# Older_Schematic.net
KiCad netlist of a schematic drawn in EAGLE
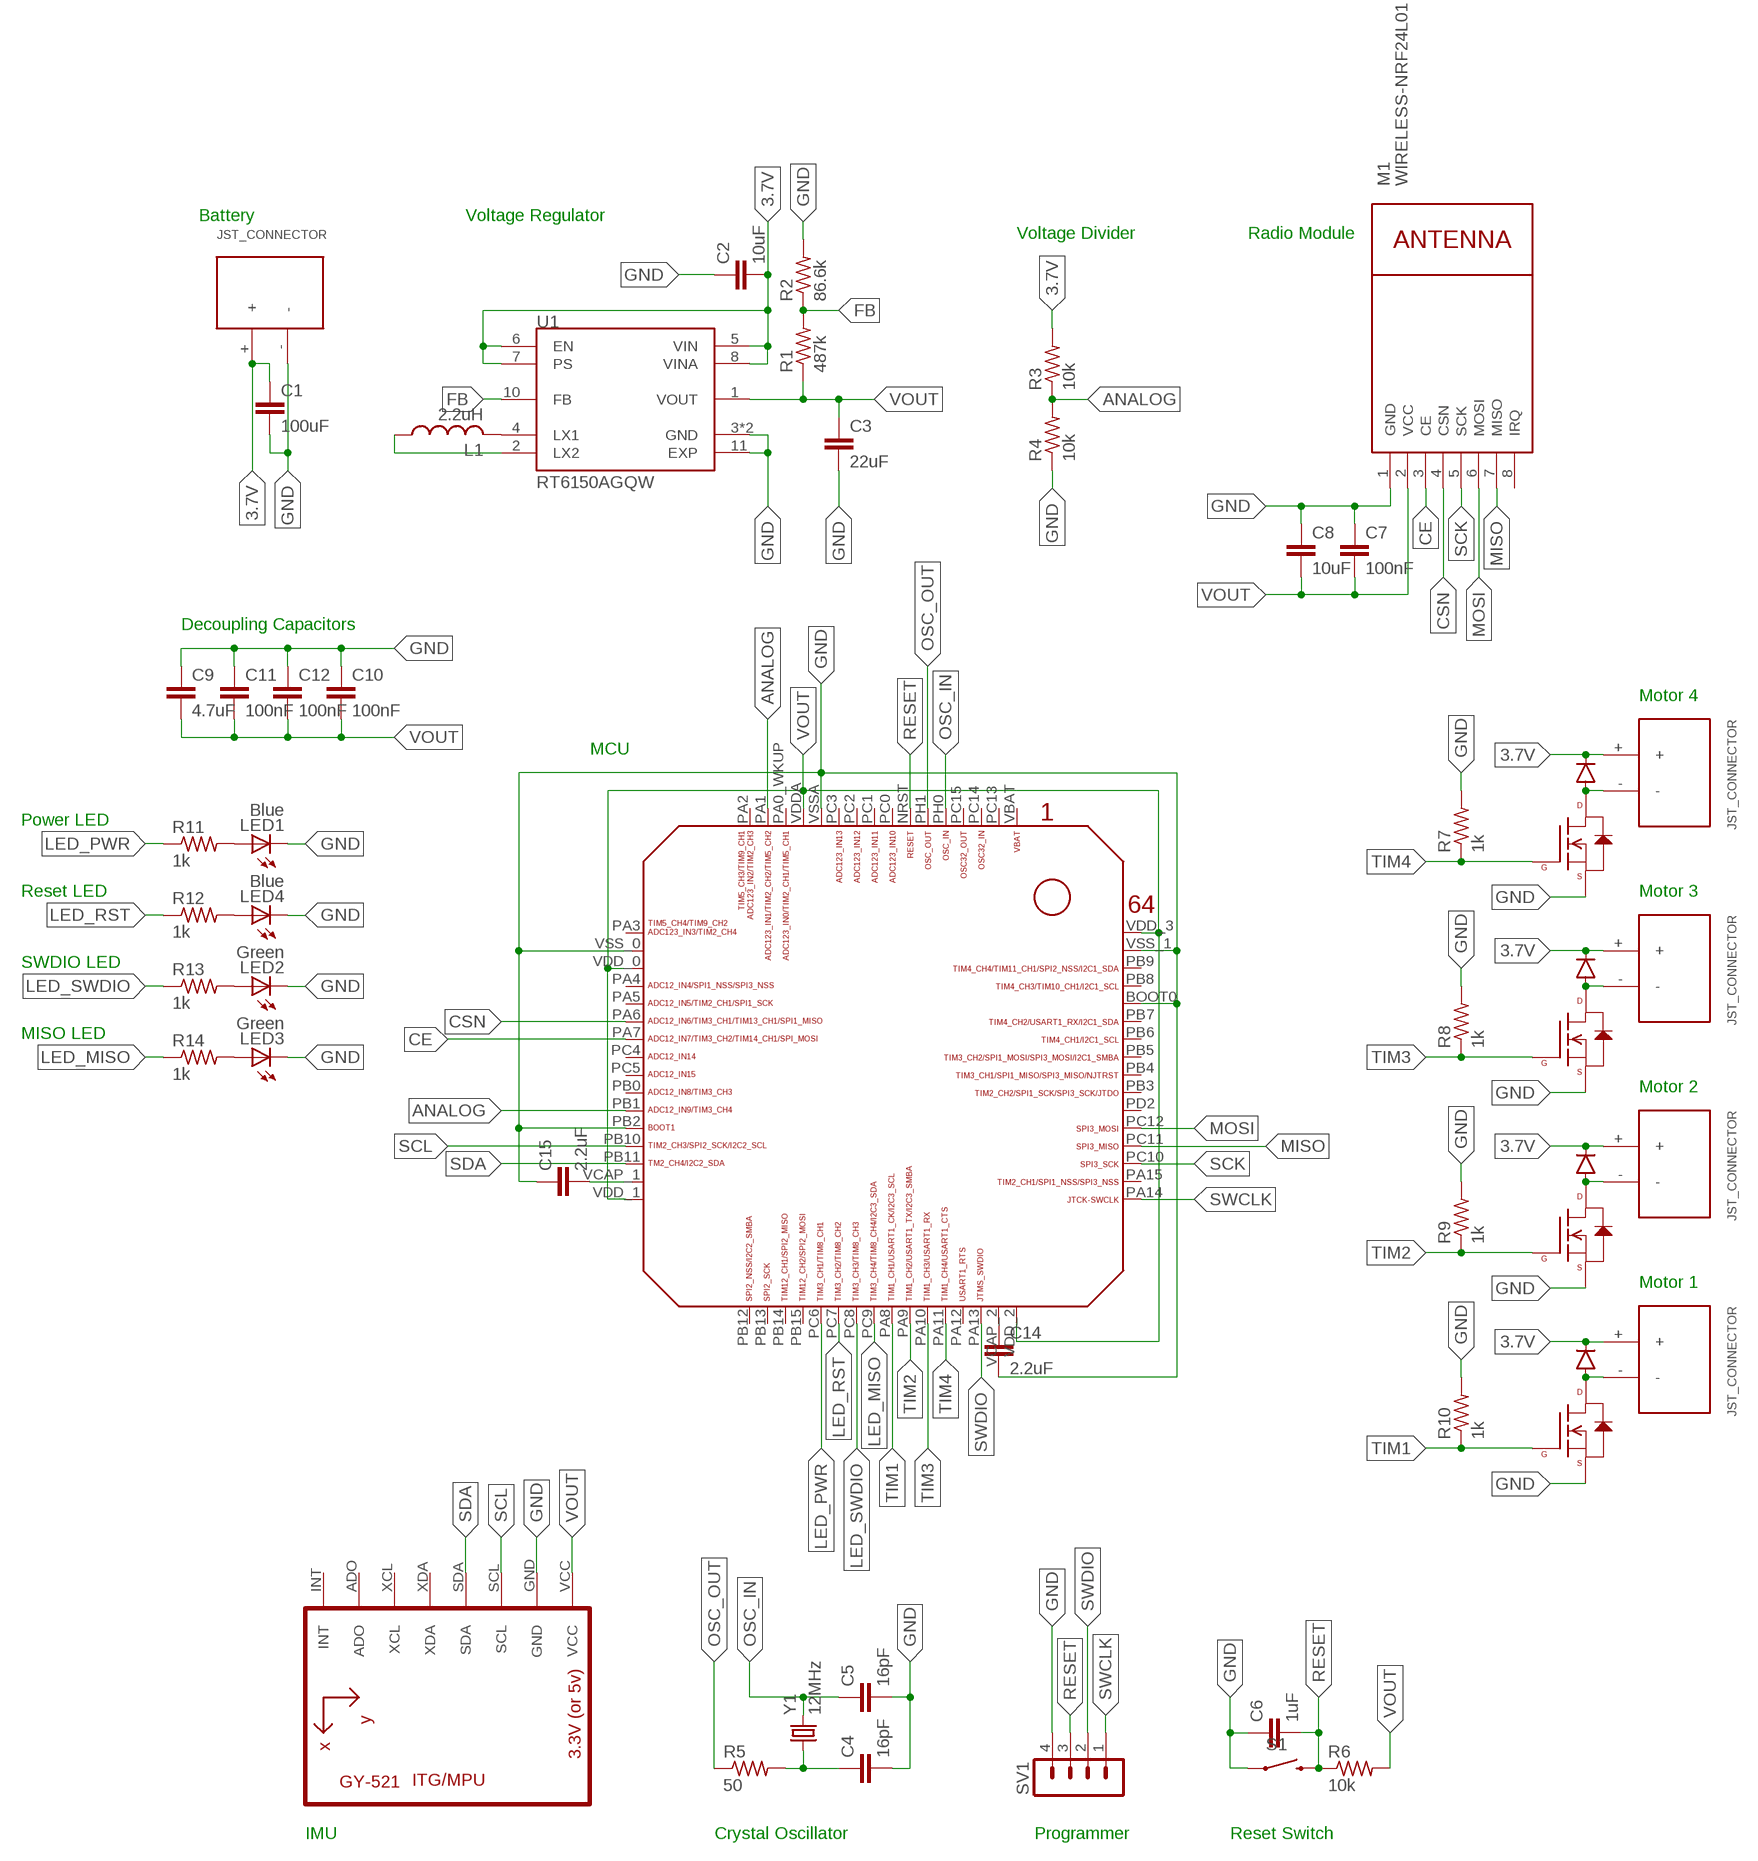
[diagram p0: schematic, sheet 1]

(export (version "E")
  (design (tool "Eeschema 10.0.6"))
  (components
    (comp (ref "C1")
      (value "100uF")
      (footprint "eagle-import:C0603")
      (libsource (lib "eagle-import") (part "rcl_334_C-EUC0603"))
    )
    (comp (ref "C2")
      (value "10uF")
      (footprint "eagle-import:C0603")
      (libsource (lib "eagle-import") (part "rcl_334_C-EUC0603"))
    )
    (comp (ref "C3")
      (value "22uF")
      (footprint "eagle-import:C0603")
      (libsource (lib "eagle-import") (part "rcl_334_C-EUC0603"))
    )
    (comp (ref "C4")
      (value "16pF")
      (footprint "eagle-import:C0603")
      (libsource (lib "eagle-import") (part "rcl_334_C-EUC0603"))
    )
    (comp (ref "C5")
      (value "16pF")
      (footprint "eagle-import:C0603")
      (libsource (lib "eagle-import") (part "rcl_334_C-EUC0603"))
    )
    (comp (ref "C6")
      (value "1uF")
      (footprint "eagle-import:C0603")
      (libsource (lib "eagle-import") (part "rcl_334_C-EUC0603"))
    )
    (comp (ref "C7")
      (value "100nF")
      (footprint "eagle-import:C0603")
      (libsource (lib "eagle-import") (part "rcl_334_C-EUC0603"))
    )
    (comp (ref "C8")
      (value "10uF")
      (footprint "eagle-import:C0603")
      (libsource (lib "eagle-import") (part "rcl_334_C-EUC0603"))
    )
    (comp (ref "C9")
      (value "4.7uF")
      (footprint "eagle-import:C0603")
      (libsource (lib "eagle-import") (part "rcl_334_C-EUC0603"))
    )
    (comp (ref "C10")
      (value "100nF")
      (footprint "eagle-import:C0603")
      (libsource (lib "eagle-import") (part "rcl_334_C-EUC0603"))
    )
    (comp (ref "C11")
      (value "100nF")
      (footprint "eagle-import:C0603")
      (libsource (lib "eagle-import") (part "rcl_334_C-EUC0603"))
    )
    (comp (ref "C12")
      (value "100nF")
      (footprint "eagle-import:C0603")
      (libsource (lib "eagle-import") (part "rcl_334_C-EUC0603"))
    )
    (comp (ref "C14")
      (value "2.2uF")
      (footprint "eagle-import:C0603")
      (libsource (lib "eagle-import") (part "C-EUC0603"))
    )
    (comp (ref "C15")
      (value "2.2uF")
      (footprint "eagle-import:C0603")
      (libsource (lib "eagle-import") (part "C-EUC0603"))
    )
    (comp (ref "L1")
      (value "2.2uH")
      (footprint "eagle-import:L0603")
      (libsource (lib "eagle-import") (part "L-USL0603"))
    )
    (comp (ref "LED1")
      (value "Blue")
      (footprint "eagle-import:CHIP-LED0603")
      (libsource (lib "eagle-import") (part "LEDCHIP-LED0603"))
    )
    (comp (ref "LED2")
      (value "Green")
      (footprint "eagle-import:CHIP-LED0603")
      (libsource (lib "eagle-import") (part "LEDCHIP-LED0603"))
    )
    (comp (ref "LED3")
      (value "Green")
      (footprint "eagle-import:CHIP-LED0603")
      (libsource (lib "eagle-import") (part "LEDCHIP-LED0603"))
    )
    (comp (ref "LED4")
      (value "Blue")
      (footprint "eagle-import:CHIP-LED0603")
      (libsource (lib "eagle-import") (part "LEDCHIP-LED0603"))
    )
    (comp (ref "M1")
      (value "WIRELESS-NRF24L01")
      (footprint "eagle-import:WIRELESS-NRF24L01")
      (libsource (lib "eagle-import") (part "WIRELESS-NRF24L01"))
    )
    (comp (ref "R1")
      (value "487k")
      (footprint "eagle-import:R0603")
      (libsource (lib "eagle-import") (part "R-US_R0603"))
    )
    (comp (ref "R2")
      (value "86.6k")
      (footprint "eagle-import:R0603")
      (libsource (lib "eagle-import") (part "R-US_R0603"))
    )
    (comp (ref "R3")
      (value "10k")
      (footprint "eagle-import:R0603")
      (libsource (lib "eagle-import") (part "R-US_R0603"))
    )
    (comp (ref "R4")
      (value "10k")
      (footprint "eagle-import:R0603")
      (libsource (lib "eagle-import") (part "R-US_R0603"))
    )
    (comp (ref "R5")
      (value "50")
      (footprint "eagle-import:R0603")
      (libsource (lib "eagle-import") (part "R-US_R0603"))
    )
    (comp (ref "R6")
      (value "10k")
      (footprint "eagle-import:R0603")
      (libsource (lib "eagle-import") (part "R-US_R0603"))
    )
    (comp (ref "R7")
      (value "1k")
      (footprint "eagle-import:R0603")
      (libsource (lib "eagle-import") (part "R-US_R0603"))
    )
    (comp (ref "R8")
      (value "1k")
      (footprint "eagle-import:R0603")
      (libsource (lib "eagle-import") (part "R-US_R0603"))
    )
    (comp (ref "R9")
      (value "1k")
      (footprint "eagle-import:R0603")
      (libsource (lib "eagle-import") (part "R-US_R0603"))
    )
    (comp (ref "R10")
      (value "1k")
      (footprint "eagle-import:R0603")
      (libsource (lib "eagle-import") (part "R-US_R0603"))
    )
    (comp (ref "R11")
      (value "1k")
      (footprint "eagle-import:R0603")
      (libsource (lib "eagle-import") (part "R-US_R0603"))
    )
    (comp (ref "R12")
      (value "1k")
      (footprint "eagle-import:R0603")
      (libsource (lib "eagle-import") (part "R-US_R0603"))
    )
    (comp (ref "R13")
      (value "1k")
      (footprint "eagle-import:R0603")
      (libsource (lib "eagle-import") (part "R-US_R0603"))
    )
    (comp (ref "R14")
      (value "1k")
      (footprint "eagle-import:R0603")
      (libsource (lib "eagle-import") (part "R-US_R0603"))
    )
    (comp (ref "S1")
      (value "SWITCH-MOMENTARY-2SMD")
      (footprint "eagle-import:TACTILE-SWITCH-SMD")
      (libsource (lib "eagle-import") (part "SWITCH-MOMENTARY-2SMD"))
    )
    (comp (ref "SV1")
      (value "MA04-1")
      (footprint "eagle-import:MA04-1")
      (libsource (lib "eagle-import") (part "MA04-1"))
    )
    (comp (ref "U$1")
      (value "STM32F405/415_LQFP64")
      (footprint "eagle-import:STM32F405_415_LQFP64")
      (libsource (lib "eagle-import") (part "STM32F405/415_LQFP64"))
    )
    (comp (ref "U$2")
      (value "JST_CONNECTOR_FEMALE")
      (footprint "eagle-import:JST_CONNECTOR_FEMALE")
      (libsource (lib "eagle-import") (part "JST_CONNECTOR_FEMALE"))
    )
    (comp (ref "U$3")
      (value "JST_CONNECTOR_FEMALE")
      (footprint "eagle-import:JST_CONNECTOR_FEMALE")
      (libsource (lib "eagle-import") (part "JST_CONNECTOR_FEMALE"))
    )
    (comp (ref "U$4")
      (value "JST_CONNECTOR_FEMALE")
      (footprint "eagle-import:JST_CONNECTOR_FEMALE")
      (libsource (lib "eagle-import") (part "JST_CONNECTOR_FEMALE"))
    )
    (comp (ref "U$5")
      (value "JST_CONNECTOR_FEMALE")
      (footprint "eagle-import:JST_CONNECTOR_FEMALE")
      (libsource (lib "eagle-import") (part "JST_CONNECTOR_FEMALE"))
    )
    (comp (ref "U$6")
      (value "JST_CONNECTOR_FEMALE")
      (footprint "eagle-import:JST_CONNECTOR_FEMALE")
      (libsource (lib "eagle-import") (part "JST_CONNECTOR_FEMALE"))
    )
    (comp (ref "U$7")
      (value "N-CHANNEL-MOSFET-IRLML6244TRPBF")
      (footprint "eagle-import:SOT23-3")
      (libsource (lib "eagle-import") (part "N-CHANNEL-MOSFET-IRLML6244TRPBF"))
    )
    (comp (ref "U$8")
      (value "N-CHANNEL-MOSFET-IRLML6244TRPBF")
      (footprint "eagle-import:SOT23-3")
      (libsource (lib "eagle-import") (part "N-CHANNEL-MOSFET-IRLML6244TRPBF"))
    )
    (comp (ref "U$9")
      (value "N-CHANNEL-MOSFET-IRLML6244TRPBF")
      (footprint "eagle-import:SOT23-3")
      (libsource (lib "eagle-import") (part "N-CHANNEL-MOSFET-IRLML6244TRPBF"))
    )
    (comp (ref "U$10")
      (value "N-CHANNEL-MOSFET-IRLML6244TRPBF")
      (footprint "eagle-import:SOT23-3")
      (libsource (lib "eagle-import") (part "N-CHANNEL-MOSFET-IRLML6244TRPBF"))
    )
    (comp (ref "U$11")
      (value "DB2W40300L")
      (footprint "eagle-import:MINI2-F3-B")
      (libsource (lib "eagle-import") (part "DB2W40300L"))
    )
    (comp (ref "U$12")
      (value "DB2W40300L")
      (footprint "eagle-import:MINI2-F3-B")
      (libsource (lib "eagle-import") (part "DB2W40300L"))
    )
    (comp (ref "U$13")
      (value "DB2W40300L")
      (footprint "eagle-import:MINI2-F3-B")
      (libsource (lib "eagle-import") (part "DB2W40300L"))
    )
    (comp (ref "U$14")
      (value "DB2W40300L")
      (footprint "eagle-import:MINI2-F3-B")
      (libsource (lib "eagle-import") (part "DB2W40300L"))
    )
    (comp (ref "U1")
      (value "RT6150AGQW")
      (footprint "eagle-import:SON50P250X250X80-11N")
      (fields (field (name "MF") "Richtek USA"))
      (libsource (lib "eagle-import") (part "RT6150AGQW"))
    )
    (comp (ref "U2")
      (value "GY-521MPU6050")
      (footprint "eagle-import:GY-521")
      (libsource (lib "eagle-import") (part "GY-521MPU6050"))
    )
    (comp (ref "Y1")
      (value "12MHz")
      (footprint "eagle-import:HC49US")
      (libsource (lib "eagle-import") (part "CRYSTALHC49US"))
    )
  )
  (nets
    (net (code "1") (name "3.7V") (class "Default")
      (node (ref "C1") (pin "1") (pinfunction "1_1") (pintype "passive"))
      (node (ref "C2") (pin "2") (pinfunction "2_2") (pintype "passive"))
      (node (ref "R3") (pin "2") (pinfunction "2_2") (pintype "passive"))
      (node (ref "U$11") (pin "NEG") (pinfunction "GPIN_NEG") (pintype "passive"))
      (node (ref "U$12") (pin "NEG") (pinfunction "GPIN_NEG") (pintype "passive"))
      (node (ref "U$13") (pin "NEG") (pinfunction "GPIN_NEG") (pintype "passive"))
      (node (ref "U$14") (pin "NEG") (pinfunction "GPIN_NEG") (pintype "passive"))
      (node (ref "U$2") (pin "+") (pinfunction "+_+") (pintype "bidirectional"))
      (node (ref "U$3") (pin "+") (pinfunction "+_+") (pintype "bidirectional"))
      (node (ref "U$4") (pin "+") (pinfunction "+_+") (pintype "bidirectional"))
      (node (ref "U$5") (pin "+") (pinfunction "+_+") (pintype "bidirectional"))
      (node (ref "U$6") (pin "+") (pinfunction "+_+") (pintype "bidirectional"))
      (node (ref "U1") (pin "5") (pinfunction "VIN_5") (pintype "power_in"))
      (node (ref "U1") (pin "6") (pinfunction "EN_6") (pintype "input"))
      (node (ref "U1") (pin "7") (pinfunction "PS_7") (pintype "input"))
      (node (ref "U1") (pin "8") (pinfunction "VINA_8") (pintype "power_in"))
    )
    (net (code "2") (name "ANALOG") (class "Default")
      (node (ref "R3") (pin "1") (pinfunction "1_1") (pintype "passive"))
      (node (ref "R4") (pin "2") (pinfunction "2_2") (pintype "passive"))
      (node (ref "U$1") (pin "PA1") (pinfunction "PA1_PA1") (pintype "bidirectional"))
      (node (ref "U$1") (pin "PB1") (pinfunction "PB1_PB1") (pintype "bidirectional"))
    )
    (net (code "3") (name "CE") (class "Default")
      (node (ref "M1") (pin "3") (pinfunction "CE_3") (pintype "bidirectional"))
      (node (ref "U$1") (pin "PA7") (pinfunction "PA7_PA7") (pintype "bidirectional"))
    )
    (net (code "4") (name "CSN") (class "Default")
      (node (ref "M1") (pin "4") (pinfunction "CSN_4") (pintype "bidirectional"))
      (node (ref "U$1") (pin "PA6") (pinfunction "PA6_PA6") (pintype "bidirectional"))
    )
    (net (code "5") (name "FB") (class "Default")
      (node (ref "R1") (pin "2") (pinfunction "2_2") (pintype "passive"))
      (node (ref "R2") (pin "1") (pinfunction "1_1") (pintype "passive"))
      (node (ref "U1") (pin "10") (pinfunction "FB_10") (pintype "input"))
    )
    (net (code "6") (name "GND") (class "Default")
      (node (ref "C1") (pin "2") (pinfunction "2_2") (pintype "passive"))
      (node (ref "C10") (pin "1") (pinfunction "1_1") (pintype "passive"))
      (node (ref "C11") (pin "1") (pinfunction "1_1") (pintype "passive"))
      (node (ref "C12") (pin "1") (pinfunction "1_1") (pintype "passive"))
      (node (ref "C14") (pin "2") (pinfunction "2_2") (pintype "passive"))
      (node (ref "C15") (pin "1") (pinfunction "1_1") (pintype "passive"))
      (node (ref "C2") (pin "1") (pinfunction "1_1") (pintype "passive"))
      (node (ref "C3") (pin "2") (pinfunction "2_2") (pintype "passive"))
      (node (ref "C4") (pin "2") (pinfunction "2_2") (pintype "passive"))
      (node (ref "C5") (pin "2") (pinfunction "2_2") (pintype "passive"))
      (node (ref "C6") (pin "1") (pinfunction "1_1") (pintype "passive"))
      (node (ref "C7") (pin "1") (pinfunction "1_1") (pintype "passive"))
      (node (ref "C8") (pin "1") (pinfunction "1_1") (pintype "passive"))
      (node (ref "C9") (pin "1") (pinfunction "1_1") (pintype "passive"))
      (node (ref "LED1") (pin "C") (pinfunction "C_C") (pintype "passive"))
      (node (ref "LED2") (pin "C") (pinfunction "C_C") (pintype "passive"))
      (node (ref "LED3") (pin "C") (pinfunction "C_C") (pintype "passive"))
      (node (ref "LED4") (pin "C") (pinfunction "C_C") (pintype "passive"))
      (node (ref "M1") (pin "1") (pinfunction "GND_1") (pintype "power_in"))
      (node (ref "R10") (pin "2") (pinfunction "2_2") (pintype "passive"))
      (node (ref "R2") (pin "2") (pinfunction "2_2") (pintype "passive"))
      (node (ref "R4") (pin "1") (pinfunction "1_1") (pintype "passive"))
      (node (ref "R7") (pin "2") (pinfunction "2_2") (pintype "passive"))
      (node (ref "R8") (pin "2") (pinfunction "2_2") (pintype "passive"))
      (node (ref "R9") (pin "2") (pinfunction "2_2") (pintype "passive"))
      (node (ref "S1") (pin "1") (pinfunction "1_1") (pintype "passive"))
      (node (ref "SV1") (pin "4") (pinfunction "4_4") (pintype "passive"))
      (node (ref "U$1") (pin "BOOT0") (pinfunction "BOOT0_BOOT0") (pintype "bidirectional"))
      (node (ref "U$1") (pin "PB2") (pinfunction "PB2_PB2") (pintype "bidirectional"))
      (node (ref "U$1") (pin "VSSA") (pinfunction "VSSA_VSSA") (pintype "bidirectional"))
      (node (ref "U$1") (pin "VSS_0") (pinfunction "VSS_0_VSS_0") (pintype "bidirectional"))
      (node (ref "U$1") (pin "VSS_1") (pinfunction "VSS_1_VSS_1") (pintype "bidirectional"))
      (node (ref "U$10") (pin "2") (pinfunction "S_2") (pintype "passive"))
      (node (ref "U$2") (pin "-") (pinfunction "-_-") (pintype "bidirectional"))
      (node (ref "U$7") (pin "2") (pinfunction "S_2") (pintype "passive"))
      (node (ref "U$8") (pin "2") (pinfunction "S_2") (pintype "passive"))
      (node (ref "U$9") (pin "2") (pinfunction "S_2") (pintype "passive"))
      (node (ref "U1") (pin "11") (pinfunction "EXP_11") (pintype "passive"))
      (node (ref "U1") (pin "3") (pinfunction "GND_3") (pintype "power_in"))
      (node (ref "U1") (pin "9") (pinfunction "GND_9") (pintype "power_in"))
      (node (ref "U2") (pin "GND") (pinfunction "GND_GND") (pintype "bidirectional"))
    )
    (net (code "7") (name "LED_MISO") (class "Default")
      (node (ref "R14") (pin "1") (pinfunction "1_1") (pintype "passive"))
      (node (ref "U$1") (pin "PC9") (pinfunction "PC9_PC9") (pintype "bidirectional"))
    )
    (net (code "8") (name "LED_PWR") (class "Default")
      (node (ref "R11") (pin "1") (pinfunction "1_1") (pintype "passive"))
      (node (ref "U$1") (pin "PC6") (pinfunction "PC6_PC6") (pintype "bidirectional"))
    )
    (net (code "9") (name "LED_RST") (class "Default")
      (node (ref "R12") (pin "1") (pinfunction "1_1") (pintype "passive"))
      (node (ref "U$1") (pin "PC7") (pinfunction "PC7_PC7") (pintype "bidirectional"))
    )
    (net (code "10") (name "LED_SWDIO") (class "Default")
      (node (ref "R13") (pin "1") (pinfunction "1_1") (pintype "passive"))
      (node (ref "U$1") (pin "PC8") (pinfunction "PC8_PC8") (pintype "bidirectional"))
    )
    (net (code "11") (name "MISO") (class "Default")
      (node (ref "M1") (pin "7") (pinfunction "MISO_7") (pintype "bidirectional"))
      (node (ref "U$1") (pin "PC11") (pinfunction "PC11_PC11") (pintype "bidirectional"))
    )
    (net (code "12") (name "MOSI") (class "Default")
      (node (ref "M1") (pin "6") (pinfunction "MOSI_6") (pintype "bidirectional"))
      (node (ref "U$1") (pin "PC12") (pinfunction "PC12_PC12") (pintype "bidirectional"))
    )
    (net (code "13") (name "Net-(C4-Pad1)") (class "Default")
      (node (ref "C4") (pin "1") (pinfunction "1_1") (pintype "passive"))
      (node (ref "R5") (pin "2") (pinfunction "2_2") (pintype "passive"))
      (node (ref "Y1") (pin "1") (pinfunction "1_1") (pintype "passive"))
    )
    (net (code "14") (name "Net-(C14-Pad1)") (class "Default")
      (node (ref "C14") (pin "1") (pinfunction "1_1") (pintype "passive"))
      (node (ref "U$1") (pin "VCAP_2") (pinfunction "VCAP_2_VCAP_2") (pintype "bidirectional"))
    )
    (net (code "15") (name "Net-(C15-Pad2)") (class "Default")
      (node (ref "C15") (pin "2") (pinfunction "2_2") (pintype "passive"))
      (node (ref "U$1") (pin "VCAP_1") (pinfunction "VCAP_1_VCAP_1") (pintype "bidirectional"))
    )
    (net (code "16") (name "Net-(LED1-PadA)") (class "Default")
      (node (ref "LED1") (pin "A") (pinfunction "A_A") (pintype "passive"))
      (node (ref "R11") (pin "2") (pinfunction "2_2") (pintype "passive"))
    )
    (net (code "17") (name "Net-(LED2-PadA)") (class "Default")
      (node (ref "LED2") (pin "A") (pinfunction "A_A") (pintype "passive"))
      (node (ref "R13") (pin "2") (pinfunction "2_2") (pintype "passive"))
    )
    (net (code "18") (name "Net-(LED3-PadA)") (class "Default")
      (node (ref "LED3") (pin "A") (pinfunction "A_A") (pintype "passive"))
      (node (ref "R14") (pin "2") (pinfunction "2_2") (pintype "passive"))
    )
    (net (code "19") (name "Net-(LED4-PadA)") (class "Default")
      (node (ref "LED4") (pin "A") (pinfunction "A_A") (pintype "passive"))
      (node (ref "R12") (pin "2") (pinfunction "2_2") (pintype "passive"))
    )
    (net (code "20") (name "Net-(U$10-D)") (class "Default")
      (node (ref "U$10") (pin "3") (pinfunction "D_3") (pintype "passive"))
      (node (ref "U$14") (pin "POS") (pinfunction "PPIN_POS") (pintype "passive"))
      (node (ref "U$6") (pin "-") (pinfunction "-_-") (pintype "bidirectional"))
    )
    (net (code "21") (name "Net-(U$11-PPIN)") (class "Default")
      (node (ref "U$11") (pin "POS") (pinfunction "PPIN_POS") (pintype "passive"))
      (node (ref "U$3") (pin "-") (pinfunction "-_-") (pintype "bidirectional"))
      (node (ref "U$9") (pin "3") (pinfunction "D_3") (pintype "passive"))
    )
    (net (code "22") (name "Net-(U$12-PPIN)") (class "Default")
      (node (ref "U$12") (pin "POS") (pinfunction "PPIN_POS") (pintype "passive"))
      (node (ref "U$5") (pin "-") (pinfunction "-_-") (pintype "bidirectional"))
      (node (ref "U$8") (pin "3") (pinfunction "D_3") (pintype "passive"))
    )
    (net (code "23") (name "Net-(U$13-PPIN)") (class "Default")
      (node (ref "U$13") (pin "POS") (pinfunction "PPIN_POS") (pintype "passive"))
      (node (ref "U$4") (pin "-") (pinfunction "-_-") (pintype "bidirectional"))
      (node (ref "U$7") (pin "3") (pinfunction "D_3") (pintype "passive"))
    )
    (net (code "24") (name "Net-(U1-LX1)") (class "Default")
      (node (ref "L1") (pin "2") (pinfunction "2_2") (pintype "passive"))
      (node (ref "U1") (pin "4") (pinfunction "LX1_4") (pintype "passive"))
    )
    (net (code "25") (name "Net-(U1-LX2)") (class "Default")
      (node (ref "L1") (pin "1") (pinfunction "1_1") (pintype "passive"))
      (node (ref "U1") (pin "2") (pinfunction "LX2_2") (pintype "passive"))
    )
    (net (code "26") (name "OSC_IN") (class "Default")
      (node (ref "C5") (pin "1") (pinfunction "1_1") (pintype "passive"))
      (node (ref "U$1") (pin "PH0") (pinfunction "PH0_PH0") (pintype "bidirectional"))
      (node (ref "Y1") (pin "2") (pinfunction "2_2") (pintype "passive"))
    )
    (net (code "27") (name "OSC_OUT") (class "Default")
      (node (ref "R5") (pin "1") (pinfunction "1_1") (pintype "passive"))
      (node (ref "U$1") (pin "PH1") (pinfunction "PH1_PH1") (pintype "bidirectional"))
    )
    (net (code "28") (name "RESET") (class "Default")
      (node (ref "C6") (pin "2") (pinfunction "2_2") (pintype "passive"))
      (node (ref "R6") (pin "1") (pinfunction "1_1") (pintype "passive"))
      (node (ref "S1") (pin "3") (pinfunction "2_3") (pintype "passive"))
      (node (ref "SV1") (pin "3") (pinfunction "3_3") (pintype "passive"))
      (node (ref "U$1") (pin "NRST") (pinfunction "NRST_NRST") (pintype "bidirectional"))
    )
    (net (code "29") (name "SCK") (class "Default")
      (node (ref "M1") (pin "5") (pinfunction "SCK_5") (pintype "bidirectional"))
      (node (ref "U$1") (pin "PC10") (pinfunction "PC10_PC10") (pintype "bidirectional"))
    )
    (net (code "30") (name "SCL") (class "Default")
      (node (ref "U$1") (pin "PB10") (pinfunction "PB10_PB10") (pintype "bidirectional"))
      (node (ref "U2") (pin "SCL") (pinfunction "SCL_SCL") (pintype "bidirectional"))
    )
    (net (code "31") (name "SDA") (class "Default")
      (node (ref "U$1") (pin "PB11") (pinfunction "PB11_PB11") (pintype "bidirectional"))
      (node (ref "U2") (pin "SDA") (pinfunction "SDA_SDA") (pintype "bidirectional"))
    )
    (net (code "32") (name "SWCLK") (class "Default")
      (node (ref "SV1") (pin "1") (pinfunction "1_1") (pintype "passive"))
      (node (ref "U$1") (pin "PA14") (pinfunction "PA14_PA14") (pintype "bidirectional"))
    )
    (net (code "33") (name "SWDIO") (class "Default")
      (node (ref "SV1") (pin "2") (pinfunction "2_2") (pintype "passive"))
      (node (ref "U$1") (pin "PA13") (pinfunction "PA13_PA13") (pintype "bidirectional"))
    )
    (net (code "34") (name "TIM1") (class "Default")
      (node (ref "R10") (pin "1") (pinfunction "1_1") (pintype "passive"))
      (node (ref "U$1") (pin "PA8") (pinfunction "PA8_PA8") (pintype "bidirectional"))
      (node (ref "U$10") (pin "1") (pinfunction "G_1") (pintype "passive"))
    )
    (net (code "35") (name "TIM2") (class "Default")
      (node (ref "R9") (pin "1") (pinfunction "1_1") (pintype "passive"))
      (node (ref "U$1") (pin "PA9") (pinfunction "PA9_PA9") (pintype "bidirectional"))
      (node (ref "U$8") (pin "1") (pinfunction "G_1") (pintype "passive"))
    )
    (net (code "36") (name "TIM3") (class "Default")
      (node (ref "R8") (pin "1") (pinfunction "1_1") (pintype "passive"))
      (node (ref "U$1") (pin "PA10") (pinfunction "PA10_PA10") (pintype "bidirectional"))
      (node (ref "U$7") (pin "1") (pinfunction "G_1") (pintype "passive"))
    )
    (net (code "37") (name "TIM4") (class "Default")
      (node (ref "R7") (pin "1") (pinfunction "1_1") (pintype "passive"))
      (node (ref "U$1") (pin "PA11") (pinfunction "PA11_PA11") (pintype "bidirectional"))
      (node (ref "U$9") (pin "1") (pinfunction "G_1") (pintype "passive"))
    )
    (net (code "38") (name "VOUT") (class "Default")
      (node (ref "C10") (pin "2") (pinfunction "2_2") (pintype "passive"))
      (node (ref "C11") (pin "2") (pinfunction "2_2") (pintype "passive"))
      (node (ref "C12") (pin "2") (pinfunction "2_2") (pintype "passive"))
      (node (ref "C3") (pin "1") (pinfunction "1_1") (pintype "passive"))
      (node (ref "C7") (pin "2") (pinfunction "2_2") (pintype "passive"))
      (node (ref "C8") (pin "2") (pinfunction "2_2") (pintype "passive"))
      (node (ref "C9") (pin "2") (pinfunction "2_2") (pintype "passive"))
      (node (ref "M1") (pin "2") (pinfunction "VCC_2") (pintype "power_in"))
      (node (ref "R1") (pin "1") (pinfunction "1_1") (pintype "passive"))
      (node (ref "R6") (pin "2") (pinfunction "2_2") (pintype "passive"))
      (node (ref "U$1") (pin "VDDA") (pinfunction "VDDA_VDDA") (pintype "bidirectional"))
      (node (ref "U$1") (pin "VDD_0") (pinfunction "VDD_0_VDD_0") (pintype "bidirectional"))
      (node (ref "U$1") (pin "VDD_1") (pinfunction "VDD_1_VDD_1") (pintype "bidirectional"))
      (node (ref "U$1") (pin "VDD_2") (pinfunction "VDD_2_VDD_2") (pintype "bidirectional"))
      (node (ref "U$1") (pin "VDD_3") (pinfunction "VDD_3_VDD_3") (pintype "bidirectional"))
      (node (ref "U1") (pin "1") (pinfunction "VOUT_1") (pintype "output"))
      (node (ref "U2") (pin "VCC") (pinfunction "VCC_VCC") (pintype "bidirectional"))
    )
    (net (code "39") (name "unconnected-(M1-IRQ-Pad8)") (class "Default")
      (node (ref "M1") (pin "8") (pinfunction "IRQ_8") (pintype "bidirectional"))
    )
    (net (code "40") (name "unconnected-(U$1-PA0_AKUP-PadPA0_WKUP)") (class "Default")
      (node (ref "U$1") (pin "PA0_WKUP") (pinfunction "PA0_AKUP_PA0_WKUP") (pintype "bidirectional"))
    )
    (net (code "41") (name "unconnected-(U$1-PadPA2)") (class "Default")
      (node (ref "U$1") (pin "PA2") (pinfunction "PA2_PA2") (pintype "bidirectional"))
    )
    (net (code "42") (name "unconnected-(U$1-PadPA3)") (class "Default")
      (node (ref "U$1") (pin "PA3") (pinfunction "PA3_PA3") (pintype "bidirectional"))
    )
    (net (code "43") (name "unconnected-(U$1-PadPA4)") (class "Default")
      (node (ref "U$1") (pin "PA4") (pinfunction "PA4_PA4") (pintype "bidirectional"))
    )
    (net (code "44") (name "unconnected-(U$1-PadPA5)") (class "Default")
      (node (ref "U$1") (pin "PA5") (pinfunction "PA5_PA5") (pintype "bidirectional"))
    )
    (net (code "45") (name "unconnected-(U$1-PadPA12)") (class "Default")
      (node (ref "U$1") (pin "PA12") (pinfunction "PA12_PA12") (pintype "bidirectional"))
    )
    (net (code "46") (name "unconnected-(U$1-PadPA15)") (class "Default")
      (node (ref "U$1") (pin "PA15") (pinfunction "PA15_PA15") (pintype "bidirectional"))
    )
    (net (code "47") (name "unconnected-(U$1-PadPB0)") (class "Default")
      (node (ref "U$1") (pin "PB0") (pinfunction "PB0_PB0") (pintype "bidirectional"))
    )
    (net (code "48") (name "unconnected-(U$1-PadPB3)") (class "Default")
      (node (ref "U$1") (pin "PB3") (pinfunction "PB3_PB3") (pintype "bidirectional"))
    )
    (net (code "49") (name "unconnected-(U$1-PadPB4)") (class "Default")
      (node (ref "U$1") (pin "PB4") (pinfunction "PB4_PB4") (pintype "bidirectional"))
    )
    (net (code "50") (name "unconnected-(U$1-PadPB5)") (class "Default")
      (node (ref "U$1") (pin "PB5") (pinfunction "PB5_PB5") (pintype "bidirectional"))
    )
    (net (code "51") (name "unconnected-(U$1-PadPB6)") (class "Default")
      (node (ref "U$1") (pin "PB6") (pinfunction "PB6_PB6") (pintype "bidirectional"))
    )
    (net (code "52") (name "unconnected-(U$1-PadPB7)") (class "Default")
      (node (ref "U$1") (pin "PB7") (pinfunction "PB7_PB7") (pintype "bidirectional"))
    )
    (net (code "53") (name "unconnected-(U$1-PadPB8)") (class "Default")
      (node (ref "U$1") (pin "PB8") (pinfunction "PB8_PB8") (pintype "bidirectional"))
    )
    (net (code "54") (name "unconnected-(U$1-PadPB9)") (class "Default")
      (node (ref "U$1") (pin "PB9") (pinfunction "PB9_PB9") (pintype "bidirectional"))
    )
    (net (code "55") (name "unconnected-(U$1-PadPB12)") (class "Default")
      (node (ref "U$1") (pin "PB12") (pinfunction "PB12_PB12") (pintype "bidirectional"))
    )
    (net (code "56") (name "unconnected-(U$1-PadPB13)") (class "Default")
      (node (ref "U$1") (pin "PB13") (pinfunction "PB13_PB13") (pintype "bidirectional"))
    )
    (net (code "57") (name "unconnected-(U$1-PadPB14)") (class "Default")
      (node (ref "U$1") (pin "PB14") (pinfunction "PB14_PB14") (pintype "bidirectional"))
    )
    (net (code "58") (name "unconnected-(U$1-PadPB15)") (class "Default")
      (node (ref "U$1") (pin "PB15") (pinfunction "PB15_PB15") (pintype "bidirectional"))
    )
    (net (code "59") (name "unconnected-(U$1-PadPC0)") (class "Default")
      (node (ref "U$1") (pin "PC0") (pinfunction "PC0_PC0") (pintype "bidirectional"))
    )
    (net (code "60") (name "unconnected-(U$1-PadPC1)") (class "Default")
      (node (ref "U$1") (pin "PC1") (pinfunction "PC1_PC1") (pintype "bidirectional"))
    )
    (net (code "61") (name "unconnected-(U$1-PadPC2)") (class "Default")
      (node (ref "U$1") (pin "PC2") (pinfunction "PC2_PC2") (pintype "bidirectional"))
    )
    (net (code "62") (name "unconnected-(U$1-PadPC3)") (class "Default")
      (node (ref "U$1") (pin "PC3") (pinfunction "PC3_PC3") (pintype "bidirectional"))
    )
    (net (code "63") (name "unconnected-(U$1-PadPC4)") (class "Default")
      (node (ref "U$1") (pin "PC4") (pinfunction "PC4_PC4") (pintype "bidirectional"))
    )
    (net (code "64") (name "unconnected-(U$1-PadPC5)") (class "Default")
      (node (ref "U$1") (pin "PC5") (pinfunction "PC5_PC5") (pintype "bidirectional"))
    )
    (net (code "65") (name "unconnected-(U$1-PadPC13)") (class "Default")
      (node (ref "U$1") (pin "PC13") (pinfunction "PC13_PC13") (pintype "bidirectional"))
    )
    (net (code "66") (name "unconnected-(U$1-PadPC14)") (class "Default")
      (node (ref "U$1") (pin "PC14") (pinfunction "PC14_PC14") (pintype "bidirectional"))
    )
    (net (code "67") (name "unconnected-(U$1-PadPC15)") (class "Default")
      (node (ref "U$1") (pin "PC15") (pinfunction "PC15_PC15") (pintype "bidirectional"))
    )
    (net (code "68") (name "unconnected-(U$1-PadPD2)") (class "Default")
      (node (ref "U$1") (pin "PD2") (pinfunction "PD2_PD2") (pintype "bidirectional"))
    )
    (net (code "69") (name "unconnected-(U$1-PadVBAT)") (class "Default")
      (node (ref "U$1") (pin "VBAT") (pinfunction "VBAT_VBAT") (pintype "bidirectional"))
    )
    (net (code "70") (name "unconnected-(U2-PadADO)") (class "Default")
      (node (ref "U2") (pin "ADO") (pinfunction "ADO_ADO") (pintype "bidirectional"))
    )
    (net (code "71") (name "unconnected-(U2-PadINT)") (class "Default")
      (node (ref "U2") (pin "INT") (pinfunction "INT_INT") (pintype "bidirectional"))
    )
    (net (code "72") (name "unconnected-(U2-PadXCL)") (class "Default")
      (node (ref "U2") (pin "XCL") (pinfunction "XCL_XCL") (pintype "bidirectional"))
    )
    (net (code "73") (name "unconnected-(U2-PadXDA)") (class "Default")
      (node (ref "U2") (pin "XDA") (pinfunction "XDA_XDA") (pintype "bidirectional"))
    )
  )
)
